# Analog_Test.net
KiCad netlist of a schematic drawn in Altium Designer
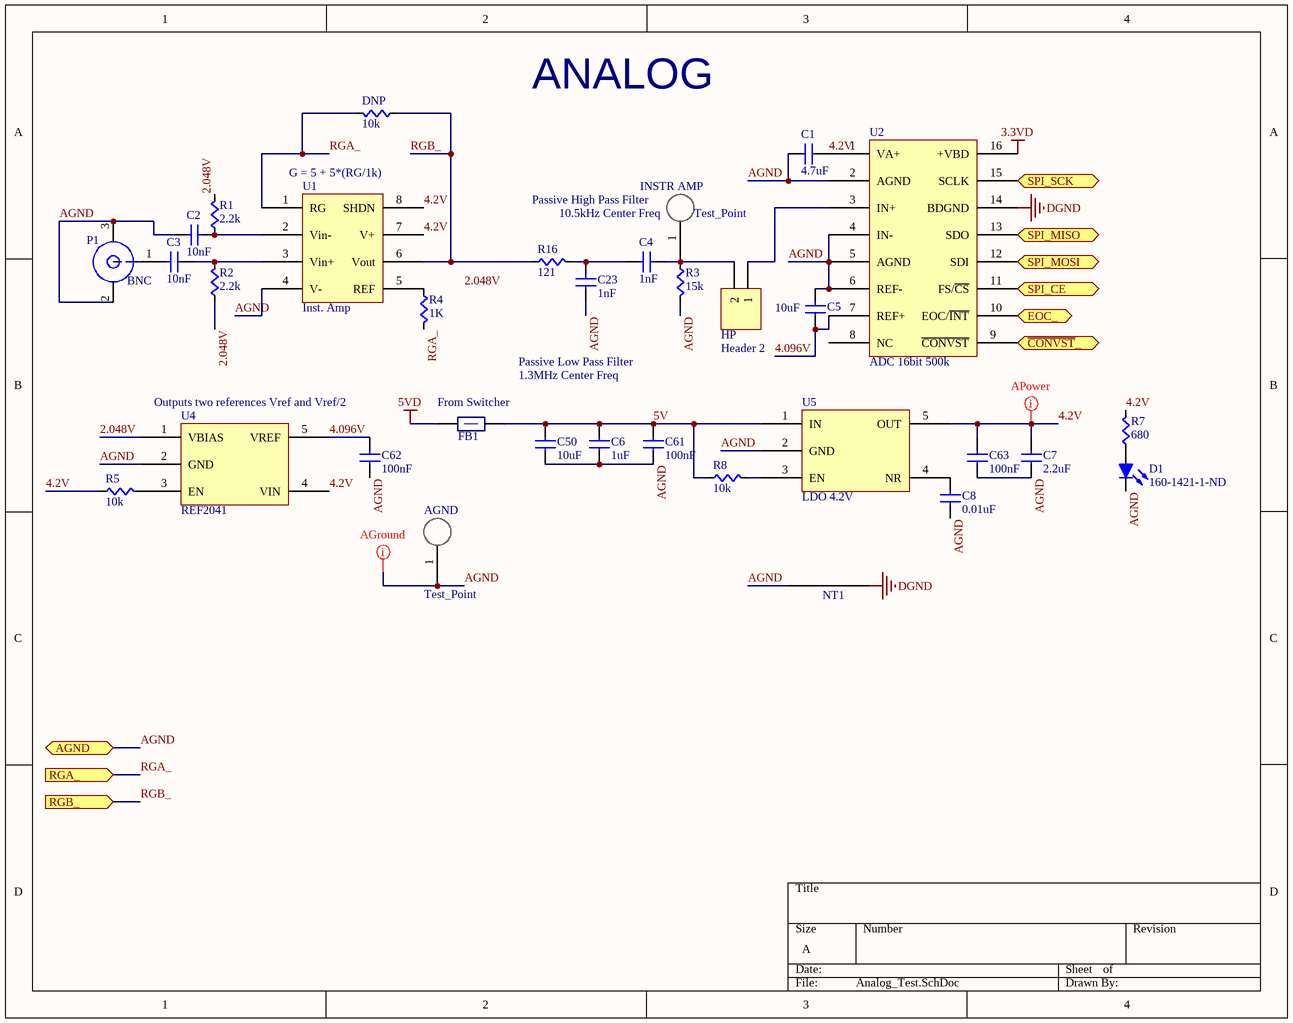
[diagram p0: Analog_Test.SchDoc]

(export (version "E")
  (design (tool "Eeschema 10.0.6"))
  (components
    (comp (ref "AGND")
      (value "Test_Point")
      (footprint "TP")
      (description "TEST POINT PC COMPACT .063\"D")
      (libsource (lib "Hydrophone") (part "Test_Point"))
    )
    (comp (ref "C1")
      (value "4.7uF")
      (footprint "CAPC0603")
      (fields (field (name "Comment") "Cap"))
      (libsource (lib "SubjuGator8") (part "Cap"))
    )
    (comp (ref "C2")
      (value "10nF")
      (footprint "CAPC0603")
      (fields (field (name "Comment") "Cap"))
      (libsource (lib "SubjuGator8") (part "Cap"))
    )
    (comp (ref "C3")
      (value "10nF")
      (footprint "CAPC0603")
      (fields (field (name "Comment") "Cap"))
      (libsource (lib "SubjuGator8") (part "Cap"))
    )
    (comp (ref "C4")
      (value "1nF")
      (footprint "CAPC0603")
      (fields (field (name "Comment") "Cap"))
      (libsource (lib "SubjuGator8") (part "Cap"))
    )
    (comp (ref "C5")
      (value "10uF")
      (footprint "CAPC0603")
      (fields (field (name "Comment") "Cap"))
      (libsource (lib "SubjuGator8") (part "Cap"))
    )
    (comp (ref "C6")
      (value "1uF")
      (footprint "CAPC0603")
      (fields (field (name "Comment") "Cap"))
      (libsource (lib "SubjuGator8") (part "Cap"))
    )
    (comp (ref "C7")
      (value "2.2uF")
      (footprint "CAPC0603")
      (fields (field (name "Comment") "Cap"))
      (libsource (lib "SubjuGator8") (part "Cap"))
    )
    (comp (ref "C8")
      (value "0.01uF")
      (footprint "CAPC0603")
      (fields (field (name "Comment") "Cap"))
      (libsource (lib "SubjuGator8") (part "Cap"))
    )
    (comp (ref "C23")
      (value "1nF")
      (footprint "CAPC0603")
      (fields (field (name "Comment") "Cap"))
      (libsource (lib "SubjuGator8") (part "Cap"))
    )
    (comp (ref "C50")
      (value "10uF")
      (footprint "CAPC0603")
      (fields (field (name "Comment") "Cap"))
      (libsource (lib "Passives") (part "Cap"))
    )
    (comp (ref "C61")
      (value "100nF")
      (footprint "CAPC0603")
      (fields (field (name "Comment") "Cap"))
      (libsource (lib "Passives") (part "Cap"))
    )
    (comp (ref "C62")
      (value "100nF")
      (footprint "CAPC0603")
      (fields (field (name "Comment") "Cap"))
      (libsource (lib "Passives") (part "Cap"))
    )
    (comp (ref "C63")
      (value "100nF")
      (footprint "CAPC0603")
      (fields (field (name "Comment") "Cap"))
      (libsource (lib "Passives") (part "Cap"))
    )
    (comp (ref "D1")
      (value "LED-RED")
      (footprint "Hydrophone:LED0805-RED")
      (description "Light Emitting Diode - RED")
      (fields
        (field (name "MANUFACTURER PART NUMBER") "LTST-C171CKT")
        (field (name "MANUFACTURER") "Lite-On Inc")
        (field (name "SUPPLIER PART NUMBER") "160-1421-1-ND")
      )
      (libsource (lib "Hydrophone") (part "LED-RED"))
    )
    (comp (ref "DNP")
      (value "10k")
      (footprint "RES0603")
      (fields (field (name "Comment") "Res"))
      (libsource (lib "SubjuGator8") (part "Res"))
    )
    (comp (ref "FB1")
      (value "FBead")
      (footprint "RES0603")
      (description "Ferrite Bead")
      (libsource (lib "Passives") (part "FBead"))
    )
    (comp (ref "HP")
      (value "Header 2")
      (footprint "HDR1X2")
      (description "Header, 2-Pin")
      (fields (field (name "PUBLISHER") "Altium Limited"))
      (libsource (lib "Miscellaneous Connectors") (part "Header 2"))
    )
    (comp (ref "INSTR AMP")
      (value "Test_Point")
      (footprint "TP")
      (description "TEST POINT PC COMPACT .063\"D")
      (libsource (lib "Hydrophone") (part "Test_Point"))
    )
    (comp (ref "NT1")
      (value "NetTie")
      (footprint "NT_5mil")
      (description "Ties two nets together")
      (libsource (lib "SubjuGator8") (part "NetTie"))
    )
    (comp (ref "P1")
      (value "BNC")
      (footprint "BNC Connector")
      (description "CONN BNC JACK R/A 50 OHM PCB")
      (libsource (lib "SubjuGator8") (part "BNC Connector"))
    )
    (comp (ref "R1")
      (value "2.2k")
      (footprint "RES0603")
      (fields (field (name "Comment") "Res"))
      (libsource (lib "SubjuGator8") (part "Res"))
    )
    (comp (ref "R2")
      (value "2.2k")
      (footprint "RES0603")
      (fields (field (name "Comment") "Res"))
      (libsource (lib "SubjuGator8") (part "Res"))
    )
    (comp (ref "R3")
      (value "15k")
      (footprint "RES0603")
      (fields (field (name "Comment") "Res"))
      (libsource (lib "SubjuGator8") (part "Res"))
    )
    (comp (ref "R4")
      (value "1K")
      (footprint "RES0603")
      (fields (field (name "Comment") "Res"))
      (libsource (lib "Passives") (part "Res"))
    )
    (comp (ref "R5")
      (value "10k")
      (footprint "RES0603")
      (fields (field (name "Comment") "Res"))
      (libsource (lib "SubjuGator8") (part "Res"))
    )
    (comp (ref "R7")
      (value "680")
      (footprint "RES0603")
      (fields (field (name "Comment") "Res"))
      (libsource (lib "SubjuGator8") (part "Res"))
    )
    (comp (ref "R8")
      (value "10k")
      (footprint "RES0603")
      (fields (field (name "Comment") "Res"))
      (libsource (lib "SubjuGator8") (part "Res"))
    )
    (comp (ref "R16")
      (value "121")
      (footprint "RES0603")
      (fields (field (name "Comment") "Res"))
      (libsource (lib "SubjuGator8") (part "Res"))
    )
    (comp (ref "U1")
      (value "Inst. Amp")
      (footprint "TSSOP-8n")
      (description "IC OPAMP INSTR 2MHZ RRO 8VSSOP")
      (libsource (lib "SubjuGator8") (part "INA331"))
    )
    (comp (ref "U2")
      (value "ADC 16bit 500k")
      (footprint "TSSOP-16pin")
      (description "IC ADC 16BIT 500KSPS 16-TSSOP")
      (libsource (lib "SubjuGator8") (part "ADC 16bit 500k"))
    )
    (comp (ref "U4")
      (value "REF2041")
      (footprint "SOT23-5")
      (description "IC VREF SERIES 2.05V/4.096V 5SOT")
      (libsource (lib "SubjuGator8") (part "REF2041"))
    )
    (comp (ref "U5")
      (value "LDO 4.2V")
      (footprint "sot23-5")
      (description "IC REG LDO 4.2V 0.2A 5SOT")
      (libsource (lib "SubjuGator8") (part "LDO 4.2V 200mA"))
    )
  )
  (nets
    (net (code "1") (name "/2.048V") (class "Default")
      (node (ref "R1") (pin "1") (pinfunction "A_1") (pintype "passive"))
      (node (ref "R2") (pin "2") (pinfunction "B_2") (pintype "passive"))
      (node (ref "U4") (pin "1") (pinfunction "VBIAS_1") (pintype "passive"))
    )
    (net (code "2") (name "/4.2V") (class "Default")
      (node (ref "C1") (pin "2") (pinfunction "B_2") (pintype "passive"))
      (node (ref "C63") (pin "1") (pinfunction "A_1") (pintype "passive"))
      (node (ref "C7") (pin "2") (pinfunction "B_2") (pintype "passive"))
      (node (ref "R5") (pin "2") (pinfunction "B_2") (pintype "passive"))
      (node (ref "R7") (pin "1") (pinfunction "A_1") (pintype "passive"))
      (node (ref "U1") (pin "7") (pinfunction "V+_7") (pintype "passive"))
      (node (ref "U1") (pin "8") (pinfunction "SHDN_8") (pintype "passive"))
      (node (ref "U2") (pin "1") (pinfunction "VA+_1") (pintype "passive"))
      (node (ref "U4") (pin "4") (pinfunction "VIN_4") (pintype "passive"))
      (node (ref "U5") (pin "5") (pinfunction "OUT_5") (pintype "passive"))
    )
    (net (code "3") (name "/4.096V") (class "Default")
      (node (ref "C5") (pin "2") (pinfunction "B_2") (pintype "passive"))
      (node (ref "C62") (pin "1") (pinfunction "A_1") (pintype "passive"))
      (node (ref "U2") (pin "7") (pinfunction "REF+_7") (pintype "passive"))
      (node (ref "U4") (pin "5") (pinfunction "VREF_5") (pintype "passive"))
    )
    (net (code "4") (name "/5V") (class "Default")
      (node (ref "C50") (pin "1") (pinfunction "A_1") (pintype "passive"))
      (node (ref "C6") (pin "2") (pinfunction "B_2") (pintype "passive"))
      (node (ref "C61") (pin "1") (pinfunction "A_1") (pintype "passive"))
      (node (ref "FB1") (pin "2") (pinfunction "B_2") (pintype "passive"))
      (node (ref "R8") (pin "2") (pinfunction "B_2") (pintype "passive"))
      (node (ref "U5") (pin "1") (pinfunction "IN_1") (pintype "passive"))
    )
    (net (code "5") (name "/AGND") (class "Default")
      (node (ref "AGND") (pin "1") (pintype "passive"))
      (node (ref "C1") (pin "1") (pinfunction "A_1") (pintype "passive"))
      (node (ref "C2") (pin "1") (pinfunction "A_1") (pintype "passive"))
      (node (ref "C23") (pin "1") (pinfunction "A_1") (pintype "passive"))
      (node (ref "C5") (pin "1") (pinfunction "A_1") (pintype "passive"))
      (node (ref "C50") (pin "2") (pinfunction "B_2") (pintype "passive"))
      (node (ref "C6") (pin "1") (pinfunction "A_1") (pintype "passive"))
      (node (ref "C61") (pin "2") (pinfunction "B_2") (pintype "passive"))
      (node (ref "C62") (pin "2") (pinfunction "B_2") (pintype "passive"))
      (node (ref "C63") (pin "2") (pinfunction "B_2") (pintype "passive"))
      (node (ref "C7") (pin "1") (pinfunction "A_1") (pintype "passive"))
      (node (ref "C8") (pin "1") (pinfunction "A_1") (pintype "passive"))
      (node (ref "D1") (pin "1") (pinfunction "K_1") (pintype "passive"))
      (node (ref "NT1") (pin "1") (pinfunction "1_1") (pintype "passive"))
      (node (ref "P1") (pin "2") (pinfunction "GND_2") (pintype "passive"))
      (node (ref "P1") (pin "3") (pinfunction "GND_3") (pintype "passive"))
      (node (ref "R3") (pin "1") (pinfunction "A_1") (pintype "passive"))
      (node (ref "U1") (pin "4") (pinfunction "V-_4") (pintype "passive"))
      (node (ref "U2") (pin "2") (pinfunction "AGND_2") (pintype "passive"))
      (node (ref "U2") (pin "4") (pinfunction "IN-_4") (pintype "passive"))
      (node (ref "U2") (pin "5") (pinfunction "AGND_5") (pintype "passive"))
      (node (ref "U2") (pin "6") (pinfunction "REF-_6") (pintype "passive"))
      (node (ref "U4") (pin "2") (pinfunction "GND_2") (pintype "passive"))
      (node (ref "U5") (pin "2") (pinfunction "GND_2") (pintype "passive"))
    )
    (net (code "6") (name "/EOC_") (class "Default")
      (node (ref "U2") (pin "10") (pinfunction "EOC/~{INT}_10") (pintype "passive"))
    )
    (net (code "7") (name "/RGA_") (class "Default")
      (node (ref "DNP") (pin "1") (pinfunction "A_1") (pintype "passive"))
      (node (ref "R4") (pin "1") (pinfunction "A_1") (pintype "passive"))
      (node (ref "U1") (pin "1") (pinfunction "RG_1") (pintype "passive"))
    )
    (net (code "8") (name "/RGB_") (class "Default")
      (node (ref "DNP") (pin "2") (pinfunction "B_2") (pintype "passive"))
      (node (ref "R16") (pin "2") (pinfunction "B_2") (pintype "passive"))
      (node (ref "U1") (pin "6") (pinfunction "Vout_6") (pintype "passive"))
    )
    (net (code "9") (name "/SPI_CE") (class "Default")
      (node (ref "U2") (pin "11") (pinfunction "FS/~{CS}_11") (pintype "passive"))
    )
    (net (code "10") (name "/SPI_MISO") (class "Default")
      (node (ref "U2") (pin "13") (pinfunction "SDO_13") (pintype "passive"))
    )
    (net (code "11") (name "/SPI_MOSI") (class "Default")
      (node (ref "U2") (pin "12") (pinfunction "SDI_12") (pintype "passive"))
    )
    (net (code "12") (name "/SPI_SCK") (class "Default")
      (node (ref "U2") (pin "15") (pinfunction "SCLK_15") (pintype "passive"))
    )
    (net (code "13") (name "/~{CONVST}_") (class "Default")
      (node (ref "U2") (pin "9") (pinfunction "~{CONVST}_9") (pintype "passive"))
    )
    (net (code "14") (name "3.3VD") (class "Default")
      (node (ref "U2") (pin "16") (pinfunction "+VBD_16") (pintype "passive"))
    )
    (net (code "15") (name "5VD") (class "Default")
      (node (ref "FB1") (pin "1") (pinfunction "A_1") (pintype "passive"))
    )
    (net (code "16") (name "DGND") (class "Default")
      (node (ref "NT1") (pin "2") (pinfunction "2_2") (pintype "passive"))
      (node (ref "U2") (pin "14") (pinfunction "BDGND_14") (pintype "passive"))
    )
    (net (code "17") (name "Net-(C2-B)") (class "Default")
      (node (ref "C2") (pin "2") (pinfunction "B_2") (pintype "passive"))
      (node (ref "R1") (pin "2") (pinfunction "B_2") (pintype "passive"))
      (node (ref "U1") (pin "2") (pinfunction "Vin-_2") (pintype "passive"))
    )
    (net (code "18") (name "Net-(C3-A)") (class "Default")
      (node (ref "C3") (pin "1") (pinfunction "A_1") (pintype "passive"))
      (node (ref "P1") (pin "1") (pinfunction "Signal_1") (pintype "passive"))
    )
    (net (code "19") (name "Net-(C3-B)") (class "Default")
      (node (ref "C3") (pin "2") (pinfunction "B_2") (pintype "passive"))
      (node (ref "R2") (pin "1") (pinfunction "A_1") (pintype "passive"))
      (node (ref "U1") (pin "3") (pinfunction "Vin+_3") (pintype "passive"))
    )
    (net (code "20") (name "Net-(C4-B)") (class "Default")
      (node (ref "C4") (pin "2") (pinfunction "B_2") (pintype "passive"))
      (node (ref "HP") (pin "2") (pinfunction "2_2") (pintype "passive"))
      (node (ref "INSTR AMP") (pin "1") (pintype "passive"))
      (node (ref "R3") (pin "2") (pinfunction "B_2") (pintype "passive"))
    )
    (net (code "21") (name "Net-(C8-B)") (class "Default")
      (node (ref "C8") (pin "2") (pinfunction "B_2") (pintype "passive"))
      (node (ref "U5") (pin "4") (pinfunction "NR_4") (pintype "passive"))
    )
    (net (code "22") (name "Net-(C23-B)") (class "Default")
      (node (ref "C23") (pin "2") (pinfunction "B_2") (pintype "passive"))
      (node (ref "C4") (pin "1") (pinfunction "A_1") (pintype "passive"))
      (node (ref "R16") (pin "1") (pinfunction "A_1") (pintype "passive"))
    )
    (net (code "23") (name "Net-(D1-A)") (class "Default")
      (node (ref "D1") (pin "2") (pinfunction "A_2") (pintype "passive"))
      (node (ref "R7") (pin "2") (pinfunction "B_2") (pintype "passive"))
    )
    (net (code "24") (name "Net-(R4-B)") (class "Default")
      (node (ref "R4") (pin "2") (pinfunction "B_2") (pintype "passive"))
      (node (ref "U1") (pin "5") (pinfunction "REF_5") (pintype "passive"))
    )
    (net (code "25") (name "Net-(R5-A)") (class "Default")
      (node (ref "R5") (pin "1") (pinfunction "A_1") (pintype "passive"))
      (node (ref "U4") (pin "3") (pinfunction "EN_3") (pintype "passive"))
    )
    (net (code "26") (name "Net-(R8-A)") (class "Default")
      (node (ref "R8") (pin "1") (pinfunction "A_1") (pintype "passive"))
      (node (ref "U5") (pin "3") (pinfunction "EN_3") (pintype "passive"))
    )
    (net (code "27") (name "Net-(U2-IN+)") (class "Default")
      (node (ref "HP") (pin "1") (pinfunction "1_1") (pintype "passive"))
      (node (ref "U2") (pin "3") (pinfunction "IN+_3") (pintype "passive"))
    )
    (net (code "28") (name "unconnected-(U2-NC-Pad8)") (class "Default")
      (node (ref "U2") (pin "8") (pinfunction "NC_8") (pintype "passive"))
    )
  )
)
